# cuk_inverter.net
KiCad netlist of a schematic drawn in EAGLE
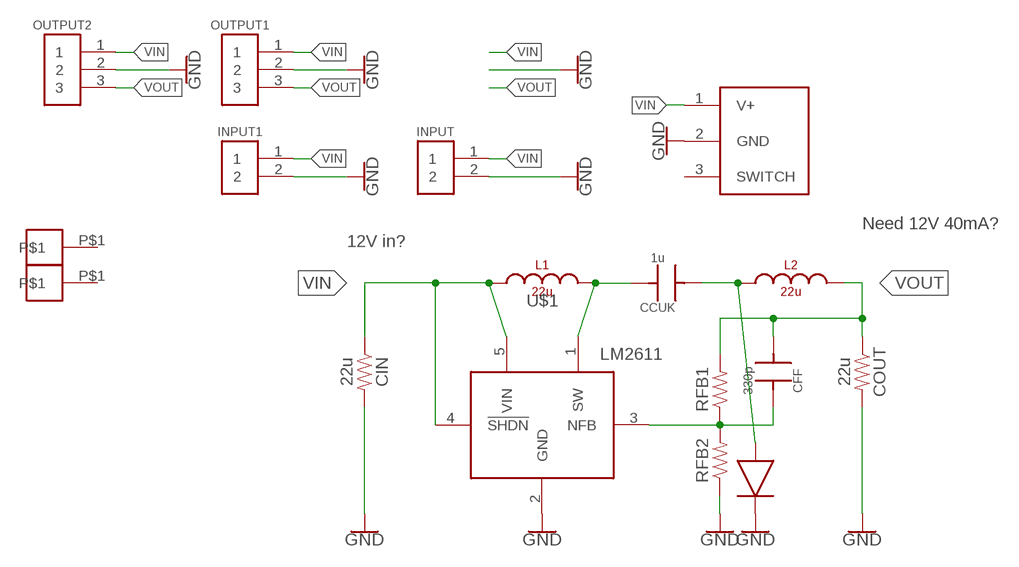
[diagram p0: schematic, sheet 1]

(export (version "E")
  (design (tool "Eeschema 10.0.6"))
  (components
    (comp (ref "CCUK")
      (value "1u")
      (footprint "eagle-import:0805_B")
      (libsource (lib "eagle-import") (part "CAP805B"))
    )
    (comp (ref "CFF")
      (value "330p")
      (footprint "eagle-import:0805_B")
      (libsource (lib "eagle-import") (part "CAP805B"))
    )
    (comp (ref "CIN")
      (value "22u")
      (footprint "eagle-import:1206")
      (libsource (lib "eagle-import") (part "RESISTOR1206"))
    )
    (comp (ref "COUT")
      (value "22u")
      (footprint "eagle-import:1206")
      (libsource (lib "eagle-import") (part "RESISTOR1206"))
    )
    (comp (ref "INPUT")
      (value "M02")
      (footprint "eagle-import:OSTVN02")
      (libsource (lib "eagle-import") (part "M02"))
    )
    (comp (ref "INPUT1")
      (value "M02")
      (footprint "eagle-import:OSTVN02")
      (libsource (lib "eagle-import") (part "M02"))
    )
    (comp (ref "L1")
      (value "22u")
      (footprint "eagle-import:INDUCTOR_BOURNS_SRU5018")
      (libsource (lib "eagle-import") (part "INDUCTORSRU5018"))
    )
    (comp (ref "L2")
      (value "22u")
      (footprint "eagle-import:INDUCTOR_BOURNS_SRU5018")
      (libsource (lib "eagle-import") (part "INDUCTORSRU5018"))
    )
    (comp (ref "OUTPUT1")
      (value "M03")
      (footprint "eagle-import:OSTVN03")
      (libsource (lib "eagle-import") (part "M03"))
    )
    (comp (ref "OUTPUT2")
      (value "M03")
      (footprint "eagle-import:OSTVN03")
      (libsource (lib "eagle-import") (part "M03"))
    )
    (comp (ref "RFB1")
      (value "RESISTOR0805")
      (footprint "eagle-import:0805")
      (libsource (lib "eagle-import") (part "RESISTOR0805"))
    )
    (comp (ref "RFB2")
      (value "RESISTOR0805")
      (footprint "eagle-import:0805")
      (libsource (lib "eagle-import") (part "RESISTOR0805"))
    )
    (comp (ref "U$1")
      (value "LM2611")
      (footprint "eagle-import:SOT-23")
      (libsource (lib "eagle-import") (part "LM2611"))
    )
    (comp (ref "U$6")
      (value "FIDUCIAL")
      (footprint "eagle-import:FIDUCIAL_0.5MM")
      (libsource (lib "eagle-import") (part "FIDUCIAL"))
    )
    (comp (ref "U$7")
      (value "FIDUCIAL")
      (footprint "eagle-import:FIDUCIAL_0.5MM")
      (libsource (lib "eagle-import") (part "FIDUCIAL"))
    )
    (comp (ref "U$8")
      (value "DIODE")
      (footprint "eagle-import:STTH3R04U")
      (libsource (lib "eagle-import") (part "DIODE"))
    )
    (comp (ref "V1")
      (value "POWER_DC_BARREL_JACKCP-102A")
      (footprint "eagle-import:CONN_JACK_POWER_2.1MM_PCB")
      (libsource (lib "eagle-import") (part "POWER_DC_BARREL_JACKCP-102A"))
    )
  )
  (nets
    (net (code "1") (name "GND") (class "Default")
      (node (ref "CIN") (pin "2") (pinfunction "2_2") (pintype "passive"))
      (node (ref "COUT") (pin "2") (pinfunction "2_2") (pintype "passive"))
      (node (ref "INPUT") (pin "2") (pinfunction "2_2") (pintype "bidirectional"))
      (node (ref "INPUT1") (pin "2") (pinfunction "2_2") (pintype "bidirectional"))
      (node (ref "OUTPUT1") (pin "2") (pinfunction "2_2") (pintype "bidirectional"))
      (node (ref "OUTPUT2") (pin "2") (pinfunction "2_2") (pintype "bidirectional"))
      (node (ref "RFB2") (pin "1") (pinfunction "1_1") (pintype "passive"))
      (node (ref "U$1") (pin "2") (pinfunction "GND_2") (pintype "bidirectional"))
      (node (ref "U$8") (pin "K") (pinfunction "K_K") (pintype "bidirectional"))
      (node (ref "V1") (pin "2") (pinfunction "GND_2") (pintype "bidirectional"))
    )
    (net (code "2") (name "Net-(L1-P$2)") (class "Default")
      (node (ref "CCUK") (pin "2") (pinfunction "2_2") (pintype "bidirectional"))
      (node (ref "L1") (pin "2") (pinfunction "P$2_2") (pintype "passive"))
      (node (ref "U$1") (pin "1") (pinfunction "SW_1") (pintype "bidirectional"))
    )
    (net (code "3") (name "Net-(L2-P$1)") (class "Default")
      (node (ref "CCUK") (pin "1") (pinfunction "1_1") (pintype "bidirectional"))
      (node (ref "L2") (pin "1") (pinfunction "P$1_1") (pintype "passive"))
      (node (ref "U$8") (pin "A") (pinfunction "A_A") (pintype "bidirectional"))
    )
    (net (code "4") (name "Net-(U$1-NFB)") (class "Default")
      (node (ref "CFF") (pin "2") (pinfunction "2_2") (pintype "bidirectional"))
      (node (ref "RFB1") (pin "1") (pinfunction "1_1") (pintype "passive"))
      (node (ref "RFB2") (pin "2") (pinfunction "2_2") (pintype "passive"))
      (node (ref "U$1") (pin "3") (pinfunction "NFB_3") (pintype "bidirectional"))
    )
    (net (code "5") (name "VIN") (class "Default")
      (node (ref "CIN") (pin "1") (pinfunction "1_1") (pintype "passive"))
      (node (ref "INPUT") (pin "1") (pinfunction "1_1") (pintype "bidirectional"))
      (node (ref "INPUT1") (pin "1") (pinfunction "1_1") (pintype "bidirectional"))
      (node (ref "L1") (pin "1") (pinfunction "P$1_1") (pintype "passive"))
      (node (ref "OUTPUT1") (pin "1") (pinfunction "1_1") (pintype "bidirectional"))
      (node (ref "OUTPUT2") (pin "1") (pinfunction "1_1") (pintype "bidirectional"))
      (node (ref "U$1") (pin "4") (pinfunction "~{SHDN}_4") (pintype "bidirectional"))
      (node (ref "U$1") (pin "5") (pinfunction "VIN_5") (pintype "bidirectional"))
      (node (ref "V1") (pin "1") (pinfunction "V+_1") (pintype "bidirectional"))
    )
    (net (code "6") (name "VOUT") (class "Default")
      (node (ref "CFF") (pin "1") (pinfunction "1_1") (pintype "bidirectional"))
      (node (ref "COUT") (pin "1") (pinfunction "1_1") (pintype "passive"))
      (node (ref "L2") (pin "2") (pinfunction "P$2_2") (pintype "passive"))
      (node (ref "OUTPUT1") (pin "3") (pinfunction "3_3") (pintype "bidirectional"))
      (node (ref "OUTPUT2") (pin "3") (pinfunction "3_3") (pintype "bidirectional"))
      (node (ref "RFB1") (pin "2") (pinfunction "2_2") (pintype "passive"))
    )
    (net (code "7") (name "unconnected-(U$6-PadP$1)") (class "Default")
      (node (ref "U$6") (pin "P$1") (pinfunction "P$1_P$1") (pintype "bidirectional"))
    )
    (net (code "8") (name "unconnected-(U$7-PadP$1)") (class "Default")
      (node (ref "U$7") (pin "P$1") (pinfunction "P$1_P$1") (pintype "bidirectional"))
    )
    (net (code "9") (name "unconnected-(V1-SWITCH-Pad3)") (class "Default")
      (node (ref "V1") (pin "3") (pinfunction "SWITCH_3") (pintype "bidirectional"))
    )
  )
)
